# FPGA_GND_NC.net
KiCad netlist of a schematic drawn in Altium Designer
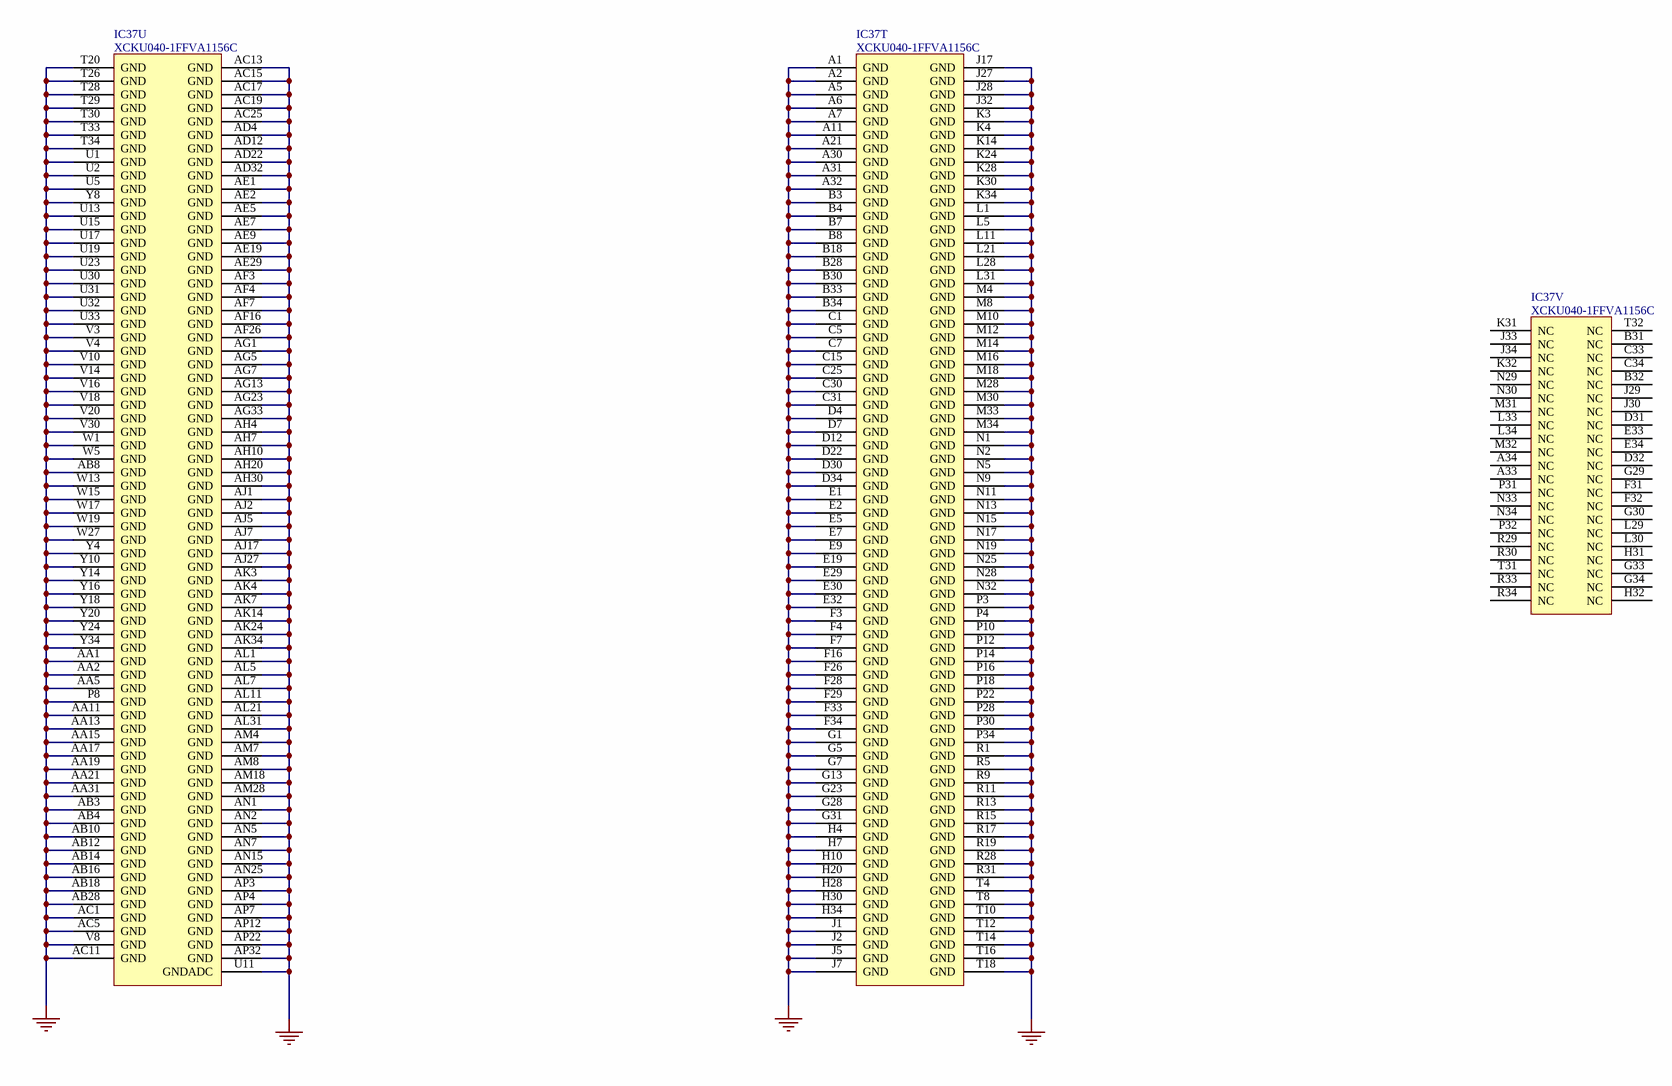
[diagram p0: FPGA_GND_NC.SchDoc]

(export (version "E")
  (design (tool "Eeschema 10.0.6"))
  (components
    (comp (ref "IC37")
      (value "XCKU040-1FFVA1156C")
      (footprint "BGA1156C100P34X34_3500X3500X350")
      (description "Kintex UltraScale FPGA, 520 I/O, 530K Cells, 1156-Ball BGA, Speed Grade 1, Commercial Grade")
      (fields (field (name "MANUFACTURER") "XILINX") (field (name "AUTHOR") "CERN DEM CA"))
      (libsource (lib "ICs And Semiconductors") (part "XCKU040-1FFVA1156C"))
    )
  )
  (nets
    (net (code "1") (name "GND") (class "Default")
      (node (ref "IC37") (pin "A1") (pinfunction "GND_A1") (pintype "power_in"))
      (node (ref "IC37") (pin "A11") (pinfunction "GND_A11") (pintype "power_in"))
      (node (ref "IC37") (pin "A2") (pinfunction "GND_A2") (pintype "power_in"))
      (node (ref "IC37") (pin "A21") (pinfunction "GND_A21") (pintype "power_in"))
      (node (ref "IC37") (pin "A30") (pinfunction "GND_A30") (pintype "power_in"))
      (node (ref "IC37") (pin "A31") (pinfunction "GND_A31") (pintype "power_in"))
      (node (ref "IC37") (pin "A32") (pinfunction "GND_A32") (pintype "power_in"))
      (node (ref "IC37") (pin "A5") (pinfunction "GND_A5") (pintype "power_in"))
      (node (ref "IC37") (pin "A6") (pinfunction "GND_A6") (pintype "power_in"))
      (node (ref "IC37") (pin "A7") (pinfunction "GND_A7") (pintype "power_in"))
      (node (ref "IC37") (pin "AA1") (pinfunction "GND_AA1") (pintype "power_in"))
      (node (ref "IC37") (pin "AA11") (pinfunction "GND_AA11") (pintype "power_in"))
      (node (ref "IC37") (pin "AA13") (pinfunction "GND_AA13") (pintype "power_in"))
      (node (ref "IC37") (pin "AA15") (pinfunction "GND_AA15") (pintype "power_in"))
      (node (ref "IC37") (pin "AA17") (pinfunction "GND_AA17") (pintype "power_in"))
      (node (ref "IC37") (pin "AA19") (pinfunction "GND_AA19") (pintype "power_in"))
      (node (ref "IC37") (pin "AA2") (pinfunction "GND_AA2") (pintype "power_in"))
      (node (ref "IC37") (pin "AA21") (pinfunction "GND_AA21") (pintype "power_in"))
      (node (ref "IC37") (pin "AA31") (pinfunction "GND_AA31") (pintype "power_in"))
      (node (ref "IC37") (pin "AA5") (pinfunction "GND_AA5") (pintype "power_in"))
      (node (ref "IC37") (pin "AB10") (pinfunction "GND_AB10") (pintype "power_in"))
      (node (ref "IC37") (pin "AB12") (pinfunction "GND_AB12") (pintype "power_in"))
      (node (ref "IC37") (pin "AB14") (pinfunction "GND_AB14") (pintype "power_in"))
      (node (ref "IC37") (pin "AB16") (pinfunction "GND_AB16") (pintype "power_in"))
      (node (ref "IC37") (pin "AB18") (pinfunction "GND_AB18") (pintype "power_in"))
      (node (ref "IC37") (pin "AB28") (pinfunction "GND_AB28") (pintype "power_in"))
      (node (ref "IC37") (pin "AB3") (pinfunction "GND_AB3") (pintype "power_in"))
      (node (ref "IC37") (pin "AB4") (pinfunction "GND_AB4") (pintype "power_in"))
      (node (ref "IC37") (pin "AB8") (pinfunction "GND_AB8") (pintype "power_in"))
      (node (ref "IC37") (pin "AC1") (pinfunction "GND_AC1") (pintype "power_in"))
      (node (ref "IC37") (pin "AC11") (pinfunction "GND_AC11") (pintype "power_in"))
      (node (ref "IC37") (pin "AC13") (pinfunction "GND_AC13") (pintype "power_in"))
      (node (ref "IC37") (pin "AC15") (pinfunction "GND_AC15") (pintype "power_in"))
      (node (ref "IC37") (pin "AC17") (pinfunction "GND_AC17") (pintype "power_in"))
      (node (ref "IC37") (pin "AC19") (pinfunction "GND_AC19") (pintype "power_in"))
      (node (ref "IC37") (pin "AC25") (pinfunction "GND_AC25") (pintype "power_in"))
      (node (ref "IC37") (pin "AC5") (pinfunction "GND_AC5") (pintype "power_in"))
      (node (ref "IC37") (pin "AD12") (pinfunction "GND_AD12") (pintype "power_in"))
      (node (ref "IC37") (pin "AD22") (pinfunction "GND_AD22") (pintype "power_in"))
      (node (ref "IC37") (pin "AD32") (pinfunction "GND_AD32") (pintype "power_in"))
      (node (ref "IC37") (pin "AD4") (pinfunction "GND_AD4") (pintype "power_in"))
      (node (ref "IC37") (pin "AE1") (pinfunction "GND_AE1") (pintype "power_in"))
      (node (ref "IC37") (pin "AE19") (pinfunction "GND_AE19") (pintype "power_in"))
      (node (ref "IC37") (pin "AE2") (pinfunction "GND_AE2") (pintype "power_in"))
      (node (ref "IC37") (pin "AE29") (pinfunction "GND_AE29") (pintype "power_in"))
      (node (ref "IC37") (pin "AE5") (pinfunction "GND_AE5") (pintype "power_in"))
      (node (ref "IC37") (pin "AE7") (pinfunction "GND_AE7") (pintype "power_in"))
      (node (ref "IC37") (pin "AE9") (pinfunction "GND_AE9") (pintype "power_in"))
      (node (ref "IC37") (pin "AF16") (pinfunction "GND_AF16") (pintype "power_in"))
      (node (ref "IC37") (pin "AF26") (pinfunction "GND_AF26") (pintype "power_in"))
      (node (ref "IC37") (pin "AF3") (pinfunction "GND_AF3") (pintype "power_in"))
      (node (ref "IC37") (pin "AF4") (pinfunction "GND_AF4") (pintype "power_in"))
      (node (ref "IC37") (pin "AF7") (pinfunction "GND_AF7") (pintype "power_in"))
      (node (ref "IC37") (pin "AG1") (pinfunction "GND_AG1") (pintype "power_in"))
      (node (ref "IC37") (pin "AG13") (pinfunction "GND_AG13") (pintype "power_in"))
      (node (ref "IC37") (pin "AG23") (pinfunction "GND_AG23") (pintype "power_in"))
      (node (ref "IC37") (pin "AG33") (pinfunction "GND_AG33") (pintype "power_in"))
      (node (ref "IC37") (pin "AG5") (pinfunction "GND_AG5") (pintype "power_in"))
      (node (ref "IC37") (pin "AG7") (pinfunction "GND_AG7") (pintype "power_in"))
      (node (ref "IC37") (pin "AH10") (pinfunction "GND_AH10") (pintype "power_in"))
      (node (ref "IC37") (pin "AH20") (pinfunction "GND_AH20") (pintype "power_in"))
      (node (ref "IC37") (pin "AH30") (pinfunction "GND_AH30") (pintype "power_in"))
      (node (ref "IC37") (pin "AH4") (pinfunction "GND_AH4") (pintype "power_in"))
      (node (ref "IC37") (pin "AH7") (pinfunction "GND_AH7") (pintype "power_in"))
      (node (ref "IC37") (pin "AJ1") (pinfunction "GND_AJ1") (pintype "power_in"))
      (node (ref "IC37") (pin "AJ17") (pinfunction "GND_AJ17") (pintype "power_in"))
      (node (ref "IC37") (pin "AJ2") (pinfunction "GND_AJ2") (pintype "power_in"))
      (node (ref "IC37") (pin "AJ27") (pinfunction "GND_AJ27") (pintype "power_in"))
      (node (ref "IC37") (pin "AJ5") (pinfunction "GND_AJ5") (pintype "power_in"))
      (node (ref "IC37") (pin "AJ7") (pinfunction "GND_AJ7") (pintype "power_in"))
      (node (ref "IC37") (pin "AK14") (pinfunction "GND_AK14") (pintype "power_in"))
      (node (ref "IC37") (pin "AK24") (pinfunction "GND_AK24") (pintype "power_in"))
      (node (ref "IC37") (pin "AK3") (pinfunction "GND_AK3") (pintype "power_in"))
      (node (ref "IC37") (pin "AK34") (pinfunction "GND_AK34") (pintype "power_in"))
      (node (ref "IC37") (pin "AK4") (pinfunction "GND_AK4") (pintype "power_in"))
      (node (ref "IC37") (pin "AK7") (pinfunction "GND_AK7") (pintype "power_in"))
      (node (ref "IC37") (pin "AL1") (pinfunction "GND_AL1") (pintype "power_in"))
      (node (ref "IC37") (pin "AL11") (pinfunction "GND_AL11") (pintype "power_in"))
      (node (ref "IC37") (pin "AL21") (pinfunction "GND_AL21") (pintype "power_in"))
      (node (ref "IC37") (pin "AL31") (pinfunction "GND_AL31") (pintype "power_in"))
      (node (ref "IC37") (pin "AL5") (pinfunction "GND_AL5") (pintype "power_in"))
      (node (ref "IC37") (pin "AL7") (pinfunction "GND_AL7") (pintype "power_in"))
      (node (ref "IC37") (pin "AM18") (pinfunction "GND_AM18") (pintype "power_in"))
      (node (ref "IC37") (pin "AM28") (pinfunction "GND_AM28") (pintype "power_in"))
      (node (ref "IC37") (pin "AM4") (pinfunction "GND_AM4") (pintype "power_in"))
      (node (ref "IC37") (pin "AM7") (pinfunction "GND_AM7") (pintype "power_in"))
      (node (ref "IC37") (pin "AM8") (pinfunction "GND_AM8") (pintype "power_in"))
      (node (ref "IC37") (pin "AN1") (pinfunction "GND_AN1") (pintype "power_in"))
      (node (ref "IC37") (pin "AN15") (pinfunction "GND_AN15") (pintype "power_in"))
      (node (ref "IC37") (pin "AN2") (pinfunction "GND_AN2") (pintype "power_in"))
      (node (ref "IC37") (pin "AN25") (pinfunction "GND_AN25") (pintype "power_in"))
      (node (ref "IC37") (pin "AN5") (pinfunction "GND_AN5") (pintype "power_in"))
      (node (ref "IC37") (pin "AN7") (pinfunction "GND_AN7") (pintype "power_in"))
      (node (ref "IC37") (pin "AP12") (pinfunction "GND_AP12") (pintype "power_in"))
      (node (ref "IC37") (pin "AP22") (pinfunction "GND_AP22") (pintype "power_in"))
      (node (ref "IC37") (pin "AP3") (pinfunction "GND_AP3") (pintype "power_in"))
      (node (ref "IC37") (pin "AP32") (pinfunction "GND_AP32") (pintype "power_in"))
      (node (ref "IC37") (pin "AP4") (pinfunction "GND_AP4") (pintype "power_in"))
      (node (ref "IC37") (pin "AP7") (pinfunction "GND_AP7") (pintype "power_in"))
      (node (ref "IC37") (pin "B18") (pinfunction "GND_B18") (pintype "power_in"))
      (node (ref "IC37") (pin "B28") (pinfunction "GND_B28") (pintype "power_in"))
      (node (ref "IC37") (pin "B3") (pinfunction "GND_B3") (pintype "power_in"))
      (node (ref "IC37") (pin "B30") (pinfunction "GND_B30") (pintype "power_in"))
      (node (ref "IC37") (pin "B33") (pinfunction "GND_B33") (pintype "power_in"))
      (node (ref "IC37") (pin "B34") (pinfunction "GND_B34") (pintype "power_in"))
      (node (ref "IC37") (pin "B4") (pinfunction "GND_B4") (pintype "power_in"))
      (node (ref "IC37") (pin "B7") (pinfunction "GND_B7") (pintype "power_in"))
      (node (ref "IC37") (pin "B8") (pinfunction "GND_B8") (pintype "power_in"))
      (node (ref "IC37") (pin "C1") (pinfunction "GND_C1") (pintype "power_in"))
      (node (ref "IC37") (pin "C15") (pinfunction "GND_C15") (pintype "power_in"))
      (node (ref "IC37") (pin "C25") (pinfunction "GND_C25") (pintype "power_in"))
      (node (ref "IC37") (pin "C30") (pinfunction "GND_C30") (pintype "power_in"))
      (node (ref "IC37") (pin "C31") (pinfunction "GND_C31") (pintype "power_in"))
      (node (ref "IC37") (pin "C5") (pinfunction "GND_C5") (pintype "power_in"))
      (node (ref "IC37") (pin "C7") (pinfunction "GND_C7") (pintype "power_in"))
      (node (ref "IC37") (pin "D12") (pinfunction "GND_D12") (pintype "power_in"))
      (node (ref "IC37") (pin "D22") (pinfunction "GND_D22") (pintype "power_in"))
      (node (ref "IC37") (pin "D30") (pinfunction "GND_D30") (pintype "power_in"))
      (node (ref "IC37") (pin "D34") (pinfunction "GND_D34") (pintype "power_in"))
      (node (ref "IC37") (pin "D4") (pinfunction "GND_D4") (pintype "power_in"))
      (node (ref "IC37") (pin "D7") (pinfunction "GND_D7") (pintype "power_in"))
      (node (ref "IC37") (pin "E1") (pinfunction "GND_E1") (pintype "power_in"))
      (node (ref "IC37") (pin "E19") (pinfunction "GND_E19") (pintype "power_in"))
      (node (ref "IC37") (pin "E2") (pinfunction "GND_E2") (pintype "power_in"))
      (node (ref "IC37") (pin "E29") (pinfunction "GND_E29") (pintype "power_in"))
      (node (ref "IC37") (pin "E30") (pinfunction "GND_E30") (pintype "power_in"))
      (node (ref "IC37") (pin "E32") (pinfunction "GND_E32") (pintype "power_in"))
      (node (ref "IC37") (pin "E5") (pinfunction "GND_E5") (pintype "power_in"))
      (node (ref "IC37") (pin "E7") (pinfunction "GND_E7") (pintype "power_in"))
      (node (ref "IC37") (pin "E9") (pinfunction "GND_E9") (pintype "power_in"))
      (node (ref "IC37") (pin "F16") (pinfunction "GND_F16") (pintype "power_in"))
      (node (ref "IC37") (pin "F26") (pinfunction "GND_F26") (pintype "power_in"))
      (node (ref "IC37") (pin "F28") (pinfunction "GND_F28") (pintype "power_in"))
      (node (ref "IC37") (pin "F29") (pinfunction "GND_F29") (pintype "power_in"))
      (node (ref "IC37") (pin "F3") (pinfunction "GND_F3") (pintype "power_in"))
      (node (ref "IC37") (pin "F33") (pinfunction "GND_F33") (pintype "power_in"))
      (node (ref "IC37") (pin "F34") (pinfunction "GND_F34") (pintype "power_in"))
      (node (ref "IC37") (pin "F4") (pinfunction "GND_F4") (pintype "power_in"))
      (node (ref "IC37") (pin "F7") (pinfunction "GND_F7") (pintype "power_in"))
      (node (ref "IC37") (pin "G1") (pinfunction "GND_G1") (pintype "power_in"))
      (node (ref "IC37") (pin "G13") (pinfunction "GND_G13") (pintype "power_in"))
      (node (ref "IC37") (pin "G23") (pinfunction "GND_G23") (pintype "power_in"))
      (node (ref "IC37") (pin "G28") (pinfunction "GND_G28") (pintype "power_in"))
      (node (ref "IC37") (pin "G31") (pinfunction "GND_G31") (pintype "power_in"))
      (node (ref "IC37") (pin "G5") (pinfunction "GND_G5") (pintype "power_in"))
      (node (ref "IC37") (pin "G7") (pinfunction "GND_G7") (pintype "power_in"))
      (node (ref "IC37") (pin "H10") (pinfunction "GND_H10") (pintype "power_in"))
      (node (ref "IC37") (pin "H20") (pinfunction "GND_H20") (pintype "power_in"))
      (node (ref "IC37") (pin "H28") (pinfunction "GND_H28") (pintype "power_in"))
      (node (ref "IC37") (pin "H30") (pinfunction "GND_H30") (pintype "power_in"))
      (node (ref "IC37") (pin "H34") (pinfunction "GND_H34") (pintype "power_in"))
      (node (ref "IC37") (pin "H4") (pinfunction "GND_H4") (pintype "power_in"))
      (node (ref "IC37") (pin "H7") (pinfunction "GND_H7") (pintype "power_in"))
      (node (ref "IC37") (pin "J1") (pinfunction "GND_J1") (pintype "power_in"))
      (node (ref "IC37") (pin "J17") (pinfunction "GND_J17") (pintype "power_in"))
      (node (ref "IC37") (pin "J2") (pinfunction "GND_J2") (pintype "power_in"))
      (node (ref "IC37") (pin "J27") (pinfunction "GND_J27") (pintype "power_in"))
      (node (ref "IC37") (pin "J28") (pinfunction "GND_J28") (pintype "power_in"))
      (node (ref "IC37") (pin "J32") (pinfunction "GND_J32") (pintype "power_in"))
      (node (ref "IC37") (pin "J5") (pinfunction "GND_J5") (pintype "power_in"))
      (node (ref "IC37") (pin "J7") (pinfunction "GND_J7") (pintype "power_in"))
      (node (ref "IC37") (pin "K14") (pinfunction "GND_K14") (pintype "power_in"))
      (node (ref "IC37") (pin "K24") (pinfunction "GND_K24") (pintype "power_in"))
      (node (ref "IC37") (pin "K28") (pinfunction "GND_K28") (pintype "power_in"))
      (node (ref "IC37") (pin "K3") (pinfunction "GND_K3") (pintype "power_in"))
      (node (ref "IC37") (pin "K30") (pinfunction "GND_K30") (pintype "power_in"))
      (node (ref "IC37") (pin "K34") (pinfunction "GND_K34") (pintype "power_in"))
      (node (ref "IC37") (pin "K4") (pinfunction "GND_K4") (pintype "power_in"))
      (node (ref "IC37") (pin "L1") (pinfunction "GND_L1") (pintype "power_in"))
      (node (ref "IC37") (pin "L11") (pinfunction "GND_L11") (pintype "power_in"))
      (node (ref "IC37") (pin "L21") (pinfunction "GND_L21") (pintype "power_in"))
      (node (ref "IC37") (pin "L28") (pinfunction "GND_L28") (pintype "power_in"))
      (node (ref "IC37") (pin "L31") (pinfunction "GND_L31") (pintype "power_in"))
      (node (ref "IC37") (pin "L5") (pinfunction "GND_L5") (pintype "power_in"))
      (node (ref "IC37") (pin "M10") (pinfunction "GND_M10") (pintype "power_in"))
      (node (ref "IC37") (pin "M12") (pinfunction "GND_M12") (pintype "power_in"))
      (node (ref "IC37") (pin "M14") (pinfunction "GND_M14") (pintype "power_in"))
      (node (ref "IC37") (pin "M16") (pinfunction "GND_M16") (pintype "power_in"))
      (node (ref "IC37") (pin "M18") (pinfunction "GND_M18") (pintype "power_in"))
      (node (ref "IC37") (pin "M28") (pinfunction "GND_M28") (pintype "power_in"))
      (node (ref "IC37") (pin "M30") (pinfunction "GND_M30") (pintype "power_in"))
      (node (ref "IC37") (pin "M33") (pinfunction "GND_M33") (pintype "power_in"))
      (node (ref "IC37") (pin "M34") (pinfunction "GND_M34") (pintype "power_in"))
      (node (ref "IC37") (pin "M4") (pinfunction "GND_M4") (pintype "power_in"))
      (node (ref "IC37") (pin "M8") (pinfunction "GND_M8") (pintype "power_in"))
      (node (ref "IC37") (pin "N1") (pinfunction "GND_N1") (pintype "power_in"))
      (node (ref "IC37") (pin "N11") (pinfunction "GND_N11") (pintype "power_in"))
      (node (ref "IC37") (pin "N13") (pinfunction "GND_N13") (pintype "power_in"))
      (node (ref "IC37") (pin "N15") (pinfunction "GND_N15") (pintype "power_in"))
      (node (ref "IC37") (pin "N17") (pinfunction "GND_N17") (pintype "power_in"))
      (node (ref "IC37") (pin "N19") (pinfunction "GND_N19") (pintype "power_in"))
      (node (ref "IC37") (pin "N2") (pinfunction "GND_N2") (pintype "power_in"))
      (node (ref "IC37") (pin "N25") (pinfunction "GND_N25") (pintype "power_in"))
      (node (ref "IC37") (pin "N28") (pinfunction "GND_N28") (pintype "power_in"))
      (node (ref "IC37") (pin "N32") (pinfunction "GND_N32") (pintype "power_in"))
      (node (ref "IC37") (pin "N5") (pinfunction "GND_N5") (pintype "power_in"))
      (node (ref "IC37") (pin "N9") (pinfunction "GND_N9") (pintype "power_in"))
      (node (ref "IC37") (pin "P10") (pinfunction "GND_P10") (pintype "power_in"))
      (node (ref "IC37") (pin "P12") (pinfunction "GND_P12") (pintype "power_in"))
      (node (ref "IC37") (pin "P14") (pinfunction "GND_P14") (pintype "power_in"))
      (node (ref "IC37") (pin "P16") (pinfunction "GND_P16") (pintype "power_in"))
      (node (ref "IC37") (pin "P18") (pinfunction "GND_P18") (pintype "power_in"))
      (node (ref "IC37") (pin "P22") (pinfunction "GND_P22") (pintype "power_in"))
      (node (ref "IC37") (pin "P28") (pinfunction "GND_P28") (pintype "power_in"))
      (node (ref "IC37") (pin "P3") (pinfunction "GND_P3") (pintype "power_in"))
      (node (ref "IC37") (pin "P30") (pinfunction "GND_P30") (pintype "power_in"))
      (node (ref "IC37") (pin "P34") (pinfunction "GND_P34") (pintype "power_in"))
      (node (ref "IC37") (pin "P4") (pinfunction "GND_P4") (pintype "power_in"))
      (node (ref "IC37") (pin "P8") (pinfunction "GND_P8") (pintype "power_in"))
      (node (ref "IC37") (pin "R1") (pinfunction "GND_R1") (pintype "power_in"))
      (node (ref "IC37") (pin "R11") (pinfunction "GND_R11") (pintype "power_in"))
      (node (ref "IC37") (pin "R13") (pinfunction "GND_R13") (pintype "power_in"))
      (node (ref "IC37") (pin "R15") (pinfunction "GND_R15") (pintype "power_in"))
      (node (ref "IC37") (pin "R17") (pinfunction "GND_R17") (pintype "power_in"))
      (node (ref "IC37") (pin "R19") (pinfunction "GND_R19") (pintype "power_in"))
      (node (ref "IC37") (pin "R28") (pinfunction "GND_R28") (pintype "power_in"))
      (node (ref "IC37") (pin "R31") (pinfunction "GND_R31") (pintype "power_in"))
      (node (ref "IC37") (pin "R5") (pinfunction "GND_R5") (pintype "power_in"))
      (node (ref "IC37") (pin "R9") (pinfunction "GND_R9") (pintype "power_in"))
      (node (ref "IC37") (pin "T10") (pinfunction "GND_T10") (pintype "power_in"))
      (node (ref "IC37") (pin "T12") (pinfunction "GND_T12") (pintype "power_in"))
      (node (ref "IC37") (pin "T14") (pinfunction "GND_T14") (pintype "power_in"))
      (node (ref "IC37") (pin "T16") (pinfunction "GND_T16") (pintype "power_in"))
      (node (ref "IC37") (pin "T18") (pinfunction "GND_T18") (pintype "power_in"))
      (node (ref "IC37") (pin "T20") (pinfunction "GND_T20") (pintype "power_in"))
      (node (ref "IC37") (pin "T26") (pinfunction "GND_T26") (pintype "power_in"))
      (node (ref "IC37") (pin "T28") (pinfunction "GND_T28") (pintype "power_in"))
      (node (ref "IC37") (pin "T29") (pinfunction "GND_T29") (pintype "power_in"))
      (node (ref "IC37") (pin "T30") (pinfunction "GND_T30") (pintype "power_in"))
      (node (ref "IC37") (pin "T33") (pinfunction "GND_T33") (pintype "power_in"))
      (node (ref "IC37") (pin "T34") (pinfunction "GND_T34") (pintype "power_in"))
      (node (ref "IC37") (pin "T4") (pinfunction "GND_T4") (pintype "power_in"))
      (node (ref "IC37") (pin "T8") (pinfunction "GND_T8") (pintype "power_in"))
      (node (ref "IC37") (pin "U1") (pinfunction "GND_U1") (pintype "power_in"))
      (node (ref "IC37") (pin "U11") (pinfunction "GNDADC_U11") (pintype "power_in"))
      (node (ref "IC37") (pin "U13") (pinfunction "GND_U13") (pintype "power_in"))
      (node (ref "IC37") (pin "U15") (pinfunction "GND_U15") (pintype "power_in"))
      (node (ref "IC37") (pin "U17") (pinfunction "GND_U17") (pintype "power_in"))
      (node (ref "IC37") (pin "U19") (pinfunction "GND_U19") (pintype "power_in"))
      (node (ref "IC37") (pin "U2") (pinfunction "GND_U2") (pintype "power_in"))
      (node (ref "IC37") (pin "U23") (pinfunction "GND_U23") (pintype "power_in"))
      (node (ref "IC37") (pin "U30") (pinfunction "GND_U30") (pintype "power_in"))
      (node (ref "IC37") (pin "U31") (pinfunction "GND_U31") (pintype "power_in"))
      (node (ref "IC37") (pin "U32") (pinfunction "GND_U32") (pintype "power_in"))
      (node (ref "IC37") (pin "U33") (pinfunction "GND_U33") (pintype "power_in"))
      (node (ref "IC37") (pin "U5") (pinfunction "GND_U5") (pintype "power_in"))
      (node (ref "IC37") (pin "V10") (pinfunction "GND_V10") (pintype "power_in"))
      (node (ref "IC37") (pin "V14") (pinfunction "GND_V14") (pintype "power_in"))
      (node (ref "IC37") (pin "V16") (pinfunction "GND_V16") (pintype "power_in"))
      (node (ref "IC37") (pin "V18") (pinfunction "GND_V18") (pintype "power_in"))
      (node (ref "IC37") (pin "V20") (pinfunction "GND_V20") (pintype "power_in"))
      (node (ref "IC37") (pin "V3") (pinfunction "GND_V3") (pintype "power_in"))
      (node (ref "IC37") (pin "V30") (pinfunction "GND_V30") (pintype "power_in"))
      (node (ref "IC37") (pin "V4") (pinfunction "GND_V4") (pintype "power_in"))
      (node (ref "IC37") (pin "V8") (pinfunction "GND_V8") (pintype "power_in"))
      (node (ref "IC37") (pin "W1") (pinfunction "GND_W1") (pintype "power_in"))
      (node (ref "IC37") (pin "W13") (pinfunction "GND_W13") (pintype "power_in"))
      (node (ref "IC37") (pin "W15") (pinfunction "GND_W15") (pintype "power_in"))
      (node (ref "IC37") (pin "W17") (pinfunction "GND_W17") (pintype "power_in"))
      (node (ref "IC37") (pin "W19") (pinfunction "GND_W19") (pintype "power_in"))
      (node (ref "IC37") (pin "W27") (pinfunction "GND_W27") (pintype "power_in"))
      (node (ref "IC37") (pin "W5") (pinfunction "GND_W5") (pintype "power_in"))
      (node (ref "IC37") (pin "Y10") (pinfunction "GND_Y10") (pintype "power_in"))
      (node (ref "IC37") (pin "Y14") (pinfunction "GND_Y14") (pintype "power_in"))
      (node (ref "IC37") (pin "Y16") (pinfunction "GND_Y16") (pintype "power_in"))
      (node (ref "IC37") (pin "Y18") (pinfunction "GND_Y18") (pintype "power_in"))
      (node (ref "IC37") (pin "Y20") (pinfunction "GND_Y20") (pintype "power_in"))
      (node (ref "IC37") (pin "Y24") (pinfunction "GND_Y24") (pintype "power_in"))
      (node (ref "IC37") (pin "Y34") (pinfunction "GND_Y34") (pintype "power_in"))
      (node (ref "IC37") (pin "Y4") (pinfunction "GND_Y4") (pintype "power_in"))
      (node (ref "IC37") (pin "Y8") (pinfunction "GND_Y8") (pintype "power_in"))
    )
    (net (code "2") (name "unconnected-(IC37V-NC-PadA33)") (class "Default")
      (node (ref "IC37") (pin "A33") (pinfunction "NC_A33") (pintype "passive"))
    )
    (net (code "3") (name "unconnected-(IC37V-NC-PadA34)") (class "Default")
      (node (ref "IC37") (pin "A34") (pinfunction "NC_A34") (pintype "passive"))
    )
    (net (code "4") (name "unconnected-(IC37V-NC-PadB31)") (class "Default")
      (node (ref "IC37") (pin "B31") (pinfunction "NC_B31") (pintype "passive"))
    )
    (net (code "5") (name "unconnected-(IC37V-NC-PadB32)") (class "Default")
      (node (ref "IC37") (pin "B32") (pinfunction "NC_B32") (pintype "passive"))
    )
    (net (code "6") (name "unconnected-(IC37V-NC-PadC33)") (class "Default")
      (node (ref "IC37") (pin "C33") (pinfunction "NC_C33") (pintype "passive"))
    )
    (net (code "7") (name "unconnected-(IC37V-NC-PadC34)") (class "Default")
      (node (ref "IC37") (pin "C34") (pinfunction "NC_C34") (pintype "passive"))
    )
    (net (code "8") (name "unconnected-(IC37V-NC-PadD31)") (class "Default")
      (node (ref "IC37") (pin "D31") (pinfunction "NC_D31") (pintype "passive"))
    )
    (net (code "9") (name "unconnected-(IC37V-NC-PadD32)") (class "Default")
      (node (ref "IC37") (pin "D32") (pinfunction "NC_D32") (pintype "passive"))
    )
    (net (code "10") (name "unconnected-(IC37V-NC-PadE33)") (class "Default")
      (node (ref "IC37") (pin "E33") (pinfunction "NC_E33") (pintype "passive"))
    )
    (net (code "11") (name "unconnected-(IC37V-NC-PadE34)") (class "Default")
      (node (ref "IC37") (pin "E34") (pinfunction "NC_E34") (pintype "passive"))
    )
    (net (code "12") (name "unconnected-(IC37V-NC-PadF31)") (class "Default")
      (node (ref "IC37") (pin "F31") (pinfunction "NC_F31") (pintype "passive"))
    )
    (net (code "13") (name "unconnected-(IC37V-NC-PadF32)") (class "Default")
      (node (ref "IC37") (pin "F32") (pinfunction "NC_F32") (pintype "passive"))
    )
    (net (code "14") (name "unconnected-(IC37V-NC-PadG29)") (class "Default")
      (node (ref "IC37") (pin "G29") (pinfunction "NC_G29") (pintype "passive"))
    )
    (net (code "15") (name "unconnected-(IC37V-NC-PadG30)") (class "Default")
      (node (ref "IC37") (pin "G30") (pinfunction "NC_G30") (pintype "passive"))
    )
    (net (code "16") (name "unconnected-(IC37V-NC-PadG33)") (class "Default")
      (node (ref "IC37") (pin "G33") (pinfunction "NC_G33") (pintype "passive"))
    )
    (net (code "17") (name "unconnected-(IC37V-NC-PadG34)") (class "Default")
      (node (ref "IC37") (pin "G34") (pinfunction "NC_G34") (pintype "passive"))
    )
    (net (code "18") (name "unconnected-(IC37V-NC-PadH31)") (class "Default")
      (node (ref "IC37") (pin "H31") (pinfunction "NC_H31") (pintype "passive"))
    )
    (net (code "19") (name "unconnected-(IC37V-NC-PadH32)") (class "Default")
      (node (ref "IC37") (pin "H32") (pinfunction "NC_H32") (pintype "passive"))
    )
    (net (code "20") (name "unconnected-(IC37V-NC-PadJ29)") (class "Default")
      (node (ref "IC37") (pin "J29") (pinfunction "NC_J29") (pintype "passive"))
    )
    (net (code "21") (name "unconnected-(IC37V-NC-PadJ30)") (class "Default")
      (node (ref "IC37") (pin "J30") (pinfunction "NC_J30") (pintype "passive"))
    )
    (net (code "22") (name "unconnected-(IC37V-NC-PadJ33)") (class "Default")
      (node (ref "IC37") (pin "J33") (pinfunction "NC_J33") (pintype "passive"))
    )
    (net (code "23") (name "unconnected-(IC37V-NC-PadJ34)") (class "Default")
      (node (ref "IC37") (pin "J34") (pinfunction "NC_J34") (pintype "passive"))
    )
    (net (code "24") (name "unconnected-(IC37V-NC-PadK31)") (class "Default")
      (node (ref "IC37") (pin "K31") (pinfunction "NC_K31") (pintype "passive"))
    )
    (net (code "25") (name "unconnected-(IC37V-NC-PadK32)") (class "Default")
      (node (ref "IC37") (pin "K32") (pinfunction "NC_K32") (pintype "passive"))
    )
    (net (code "26") (name "unconnected-(IC37V-NC-PadL29)") (class "Default")
      (node (ref "IC37") (pin "L29") (pinfunction "NC_L29") (pintype "passive"))
    )
    (net (code "27") (name "unconnected-(IC37V-NC-PadL30)") (class "Default")
      (node (ref "IC37") (pin "L30") (pinfunction "NC_L30") (pintype "passive"))
    )
    (net (code "28") (name "unconnected-(IC37V-NC-PadL33)") (class "Default")
      (node (ref "IC37") (pin "L33") (pinfunction "NC_L33") (pintype "passive"))
    )
    (net (code "29") (name "unconnected-(IC37V-NC-PadL34)") (class "Default")
      (node (ref "IC37") (pin "L34") (pinfunction "NC_L34") (pintype "passive"))
    )
    (net (code "30") (name "unconnected-(IC37V-NC-PadM31)") (class "Default")
      (node (ref "IC37") (pin "M31") (pinfunction "NC_M31") (pintype "passive"))
    )
    (net (code "31") (name "unconnected-(IC37V-NC-PadM32)") (class "Default")
      (node (ref "IC37") (pin "M32") (pinfunction "NC_M32") (pintype "passive"))
    )
    (net (code "32") (name "unconnected-(IC37V-NC-PadN29)") (class "Default")
      (node (ref "IC37") (pin "N29") (pinfunction "NC_N29") (pintype "passive"))
    )
    (net (code "33") (name "unconnected-(IC37V-NC-PadN30)") (class "Default")
      (node (ref "IC37") (pin "N30") (pinfunction "NC_N30") (pintype "passive"))
    )
    (net (code "34") (name "unconnected-(IC37V-NC-PadN33)") (class "Default")
      (node (ref "IC37") (pin "N33") (pinfunction "NC_N33") (pintype "passive"))
    )
    (net (code "35") (name "unconnected-(IC37V-NC-PadN34)") (class "Default")
      (node (ref "IC37") (pin "N34") (pinfunction "NC_N34") (pintype "passive"))
    )
    (net (code "36") (name "unconnected-(IC37V-NC-PadP31)") (class "Default")
      (node (ref "IC37") (pin "P31") (pinfunction "NC_P31") (pintype "passive"))
    )
    (net (code "37") (name "unconnected-(IC37V-NC-PadP32)") (class "Default")
      (node (ref "IC37") (pin "P32") (pinfunction "NC_P32") (pintype "passive"))
    )
    (net (code "38") (name "unconnected-(IC37V-NC-PadR29)") (class "Default")
      (node (ref "IC37") (pin "R29") (pinfunction "NC_R29") (pintype "passive"))
    )
    (net (code "39") (name "unconnected-(IC37V-NC-PadR30)") (class "Default")
      (node (ref "IC37") (pin "R30") (pinfunction "NC_R30") (pintype "passive"))
    )
    (net (code "40") (name "unconnected-(IC37V-NC-PadR33)") (class "Default")
      (node (ref "IC37") (pin "R33") (pinfunction "NC_R33") (pintype "passive"))
    )
    (net (code "41") (name "unconnected-(IC37V-NC-PadR34)") (class "Default")
      (node (ref "IC37") (pin "R34") (pinfunction "NC_R34") (pintype "passive"))
    )
    (net (code "42") (name "unconnected-(IC37V-NC-PadT31)") (class "Default")
      (node (ref "IC37") (pin "T31") (pinfunction "NC_T31") (pintype "passive"))
    )
    (net (code "43") (name "unconnected-(IC37V-NC-PadT32)") (class "Default")
      (node (ref "IC37") (pin "T32") (pinfunction "NC_T32") (pintype "passive"))
    )
  )
)
